# amplification.net
KiCad netlist of a schematic drawn in Altium Designer
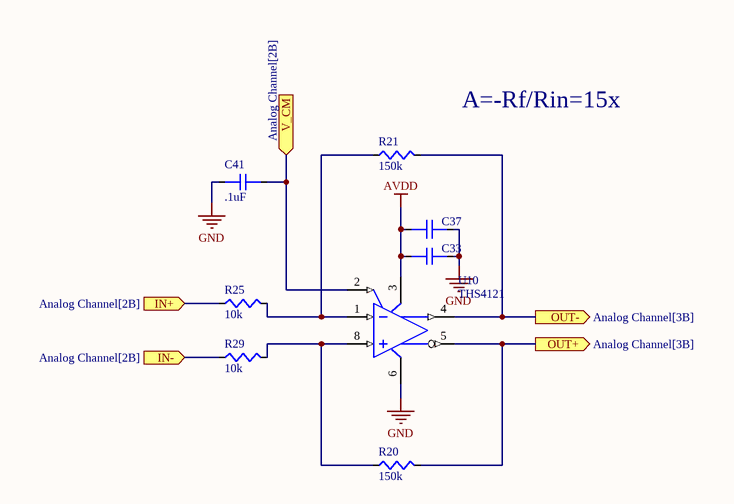
[diagram p0: amplification.SchDoc]

(export (version "E")
  (design (tool "Eeschema 10.0.6"))
  (components
    (comp (ref "C33")
      (value ".1uF")
      (footprint "C0603")
      (description "0603 0.1 uF 16 V ±5 % Tolerance X7R SMT Multilayer Ceramic Chip Capacitor")
      (fields (field (name "TOLERANCE") "5%"))
      (libsource (lib "DAQ") (part "VJ0603Y104JXJCW1BC"))
    )
    (comp (ref "C37")
      (value "2.2uF")
      (footprint "C0603")
      (description "Cap Ceramic 0.22uF 16V X7R 10% SMD 0603 125C Paper T/R")
      (fields (field (name "TOLERANCE") "10%"))
      (libsource (lib "DAQ") (part "VJ0603Y224KXJCW1BC"))
    )
    (comp (ref "C41")
      (value ".1uF")
      (footprint "C0603")
      (description "0603 0.1 uF 16 V ±5 % Tolerance X7R SMT Multilayer Ceramic Chip Capacitor")
      (fields (field (name "TOLERANCE") "5%"))
      (libsource (lib "DAQ") (part "VJ0603Y104JXJCW1BC"))
    )
    (comp (ref "R20")
      (value "150k")
      (footprint "R0603")
      (description "CRGCQ 0603 150K 1%")
      (fields (field (name "TOLERANCE") "5%"))
      (libsource (lib "DAQ") (part "CRGCQ0603F150K"))
    )
    (comp (ref "R21")
      (value "150k")
      (footprint "R0603")
      (description "CRGCQ 0603 150K 1%")
      (fields (field (name "TOLERANCE") "5%"))
      (libsource (lib "DAQ") (part "CRGCQ0603F150K"))
    )
    (comp (ref "R25")
      (value "10k")
      (footprint "R0603")
      (description "RES SMD 10K OHM 5% 1/10W 0603")
      (libsource (lib "DAQ") (part "RC0603JR-0710KL"))
    )
    (comp (ref "R29")
      (value "10k")
      (footprint "R0603")
      (description "RES SMD 10K OHM 5% 1/10W 0603")
      (libsource (lib "DAQ") (part "RC0603JR-0710KL"))
    )
    (comp (ref "U10")
      (value "THS4121")
      (footprint "DGN8_1P89X1P57-L")
      (description "IC OPAMP DIFF 1 CIRCUIT 8MSOP")
      (libsource (lib "DAQ") (part "THS4121"))
    )
  )
  (nets
    (net (code "1") (name "/IN+") (class "Default")
      (node (ref "R25") (pin "1") (pinfunction "1_1") (pintype "passive"))
    )
    (net (code "2") (name "/IN-") (class "Default")
      (node (ref "R29") (pin "1") (pinfunction "1_1") (pintype "passive"))
    )
    (net (code "3") (name "/OUT+") (class "Default")
      (node (ref "R20") (pin "2") (pinfunction "2_2") (pintype "passive"))
      (node (ref "U10") (pin "5") (pinfunction "VOUT-_5") (pintype "output"))
    )
    (net (code "4") (name "/OUT-") (class "Default")
      (node (ref "R21") (pin "2") (pinfunction "2_2") (pintype "passive"))
      (node (ref "U10") (pin "4") (pinfunction "VOUT+_4") (pintype "output"))
    )
    (net (code "5") (name "/V_CM") (class "Default")
      (node (ref "C41") (pin "2") (pinfunction "2_2") (pintype "passive"))
      (node (ref "U10") (pin "2") (pinfunction "VOCM_2") (pintype "input"))
    )
    (net (code "6") (name "AVDD") (class "Default")
      (node (ref "C33") (pin "1") (pinfunction "1_1") (pintype "passive"))
      (node (ref "C37") (pin "1") (pinfunction "1_1") (pintype "passive"))
      (node (ref "U10") (pin "3") (pinfunction "VS+_3") (pintype "power_in"))
    )
    (net (code "7") (name "GND") (class "Default")
      (node (ref "C33") (pin "2") (pinfunction "2_2") (pintype "passive"))
      (node (ref "C37") (pin "2") (pinfunction "2_2") (pintype "passive"))
      (node (ref "C41") (pin "1") (pinfunction "1_1") (pintype "passive"))
      (node (ref "U10") (pin "6") (pinfunction "VS-_6") (pintype "power_in"))
    )
    (net (code "8") (name "Net-(U10-VIN+)") (class "Default")
      (node (ref "R20") (pin "1") (pinfunction "1_1") (pintype "passive"))
      (node (ref "R29") (pin "2") (pinfunction "2_2") (pintype "passive"))
      (node (ref "U10") (pin "8") (pinfunction "VIN+_8") (pintype "input"))
    )
    (net (code "9") (name "Net-(U10-VIN-)") (class "Default")
      (node (ref "R21") (pin "1") (pinfunction "1_1") (pintype "passive"))
      (node (ref "R25") (pin "2") (pinfunction "2_2") (pintype "passive"))
      (node (ref "U10") (pin "1") (pinfunction "VIN-_1") (pintype "input"))
    )
  )
)
